# temperature.net
KiCad netlist of a schematic drawn in EAGLE
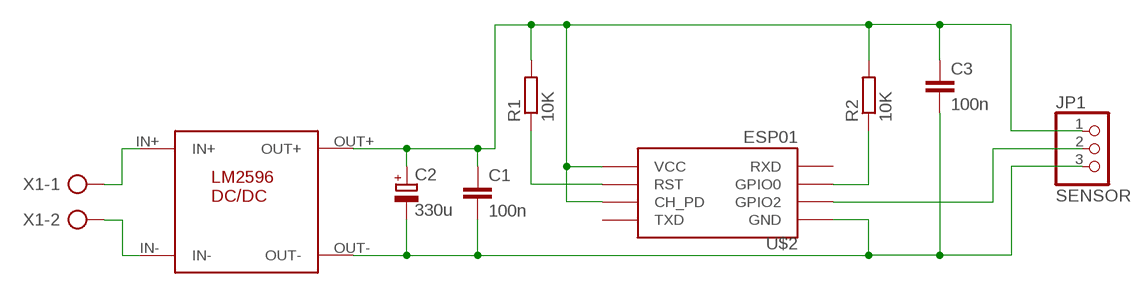
[diagram p0: schematic, sheet 1]

(export (version "E")
  (design (tool "Eeschema 10.0.6"))
  (components
    (comp (ref "C1")
      (value "100n")
      (footprint "eagle-import:C050-024X044")
      (libsource (lib "eagle-import") (part "C-EU050-024X044"))
    )
    (comp (ref "C2")
      (value "330u")
      (footprint "eagle-import:E2,5-6E")
      (libsource (lib "eagle-import") (part "CPOL-EUE2,5-6E"))
    )
    (comp (ref "C3")
      (value "100n")
      (footprint "eagle-import:C050-024X044")
      (libsource (lib "eagle-import") (part "C-EU050-024X044"))
    )
    (comp (ref "JP1")
      (value "SENSOR")
      (footprint "eagle-import:1X03")
      (libsource (lib "eagle-import") (part "PINHD-1X3"))
    )
    (comp (ref "R1")
      (value "10K")
      (footprint "eagle-import:0204_7")
      (libsource (lib "eagle-import") (part "R-EU_0204/7"))
    )
    (comp (ref "R2")
      (value "10K")
      (footprint "eagle-import:0204_7")
      (libsource (lib "eagle-import") (part "R-EU_0204/7"))
    )
    (comp (ref "U$1")
      (value "LM2596DCDC")
      (footprint "eagle-import:LM2596DCDC")
      (libsource (lib "eagle-import") (part "LM2596DCDC"))
    )
    (comp (ref "U$2")
      (value "ESP01")
      (footprint "eagle-import:ESP01")
      (libsource (lib "eagle-import") (part "ESP01"))
    )
    (comp (ref "X1")
      (value "AK300/2")
      (footprint "eagle-import:AK300_2")
      (libsource (lib "eagle-import") (part "AK300/2"))
    )
  )
  (nets
    (net (code "1") (name "Net-(C1-Pad1)") (class "Default")
      (node (ref "C1") (pin "1") (pinfunction "1_1") (pintype "passive"))
      (node (ref "C2") (pin "+") (pinfunction "+_+") (pintype "passive"))
      (node (ref "C3") (pin "1") (pinfunction "1_1") (pintype "passive"))
      (node (ref "JP1") (pin "1") (pinfunction "1_1") (pintype "passive"))
      (node (ref "R1") (pin "2") (pinfunction "2_2") (pintype "passive"))
      (node (ref "R2") (pin "2") (pinfunction "2_2") (pintype "passive"))
      (node (ref "U$1") (pin "OUT+") (pinfunction "OUT+_OUT+") (pintype "bidirectional"))
      (node (ref "U$2") (pin "CH_PD") (pinfunction "CH_PD_CH_PD") (pintype "bidirectional"))
      (node (ref "U$2") (pin "VCC") (pinfunction "VCC_VCC") (pintype "bidirectional"))
    )
    (net (code "2") (name "Net-(C1-Pad2)") (class "Default")
      (node (ref "C1") (pin "2") (pinfunction "2_2") (pintype "passive"))
      (node (ref "C2") (pin "-") (pinfunction "-_-") (pintype "passive"))
      (node (ref "C3") (pin "2") (pinfunction "2_2") (pintype "passive"))
      (node (ref "JP1") (pin "3") (pinfunction "3_3") (pintype "passive"))
      (node (ref "U$1") (pin "OUT-") (pinfunction "OUT-_OUT-") (pintype "bidirectional"))
      (node (ref "U$2") (pin "GND") (pinfunction "GND_GND") (pintype "bidirectional"))
    )
    (net (code "3") (name "Net-(JP1-Pad2)") (class "Default")
      (node (ref "JP1") (pin "2") (pinfunction "2_2") (pintype "passive"))
      (node (ref "U$2") (pin "GPIO2") (pinfunction "GPIO2_GPIO2") (pintype "bidirectional"))
    )
    (net (code "4") (name "Net-(R1-Pad1)") (class "Default")
      (node (ref "R1") (pin "1") (pinfunction "1_1") (pintype "passive"))
      (node (ref "U$2") (pin "RST") (pinfunction "RST_RST") (pintype "bidirectional"))
    )
    (net (code "5") (name "Net-(R2-Pad1)") (class "Default")
      (node (ref "R2") (pin "1") (pinfunction "1_1") (pintype "passive"))
      (node (ref "U$2") (pin "GPIO0") (pinfunction "GPIO0_GPIO0") (pintype "bidirectional"))
    )
    (net (code "6") (name "Net-(X1A-KL)") (class "Default")
      (node (ref "U$1") (pin "IN+") (pinfunction "IN+_IN+") (pintype "bidirectional"))
      (node (ref "X1") (pin "1") (pinfunction "KL_1") (pintype "passive"))
    )
    (net (code "7") (name "Net-(X1B-KL)") (class "Default")
      (node (ref "U$1") (pin "IN-") (pinfunction "IN-_IN-") (pintype "bidirectional"))
      (node (ref "X1") (pin "2") (pinfunction "KL_2") (pintype "passive"))
    )
    (net (code "8") (name "unconnected-(U$2-RXD-PadRX)") (class "Default")
      (node (ref "U$2") (pin "RX") (pinfunction "RXD_RX") (pintype "bidirectional"))
    )
    (net (code "9") (name "unconnected-(U$2-TXD-PadTX)") (class "Default")
      (node (ref "U$2") (pin "TX") (pinfunction "TXD_TX") (pintype "bidirectional"))
    )
  )
)
